# kaimat.net
KiCad netlist of a schematic drawn in EAGLE
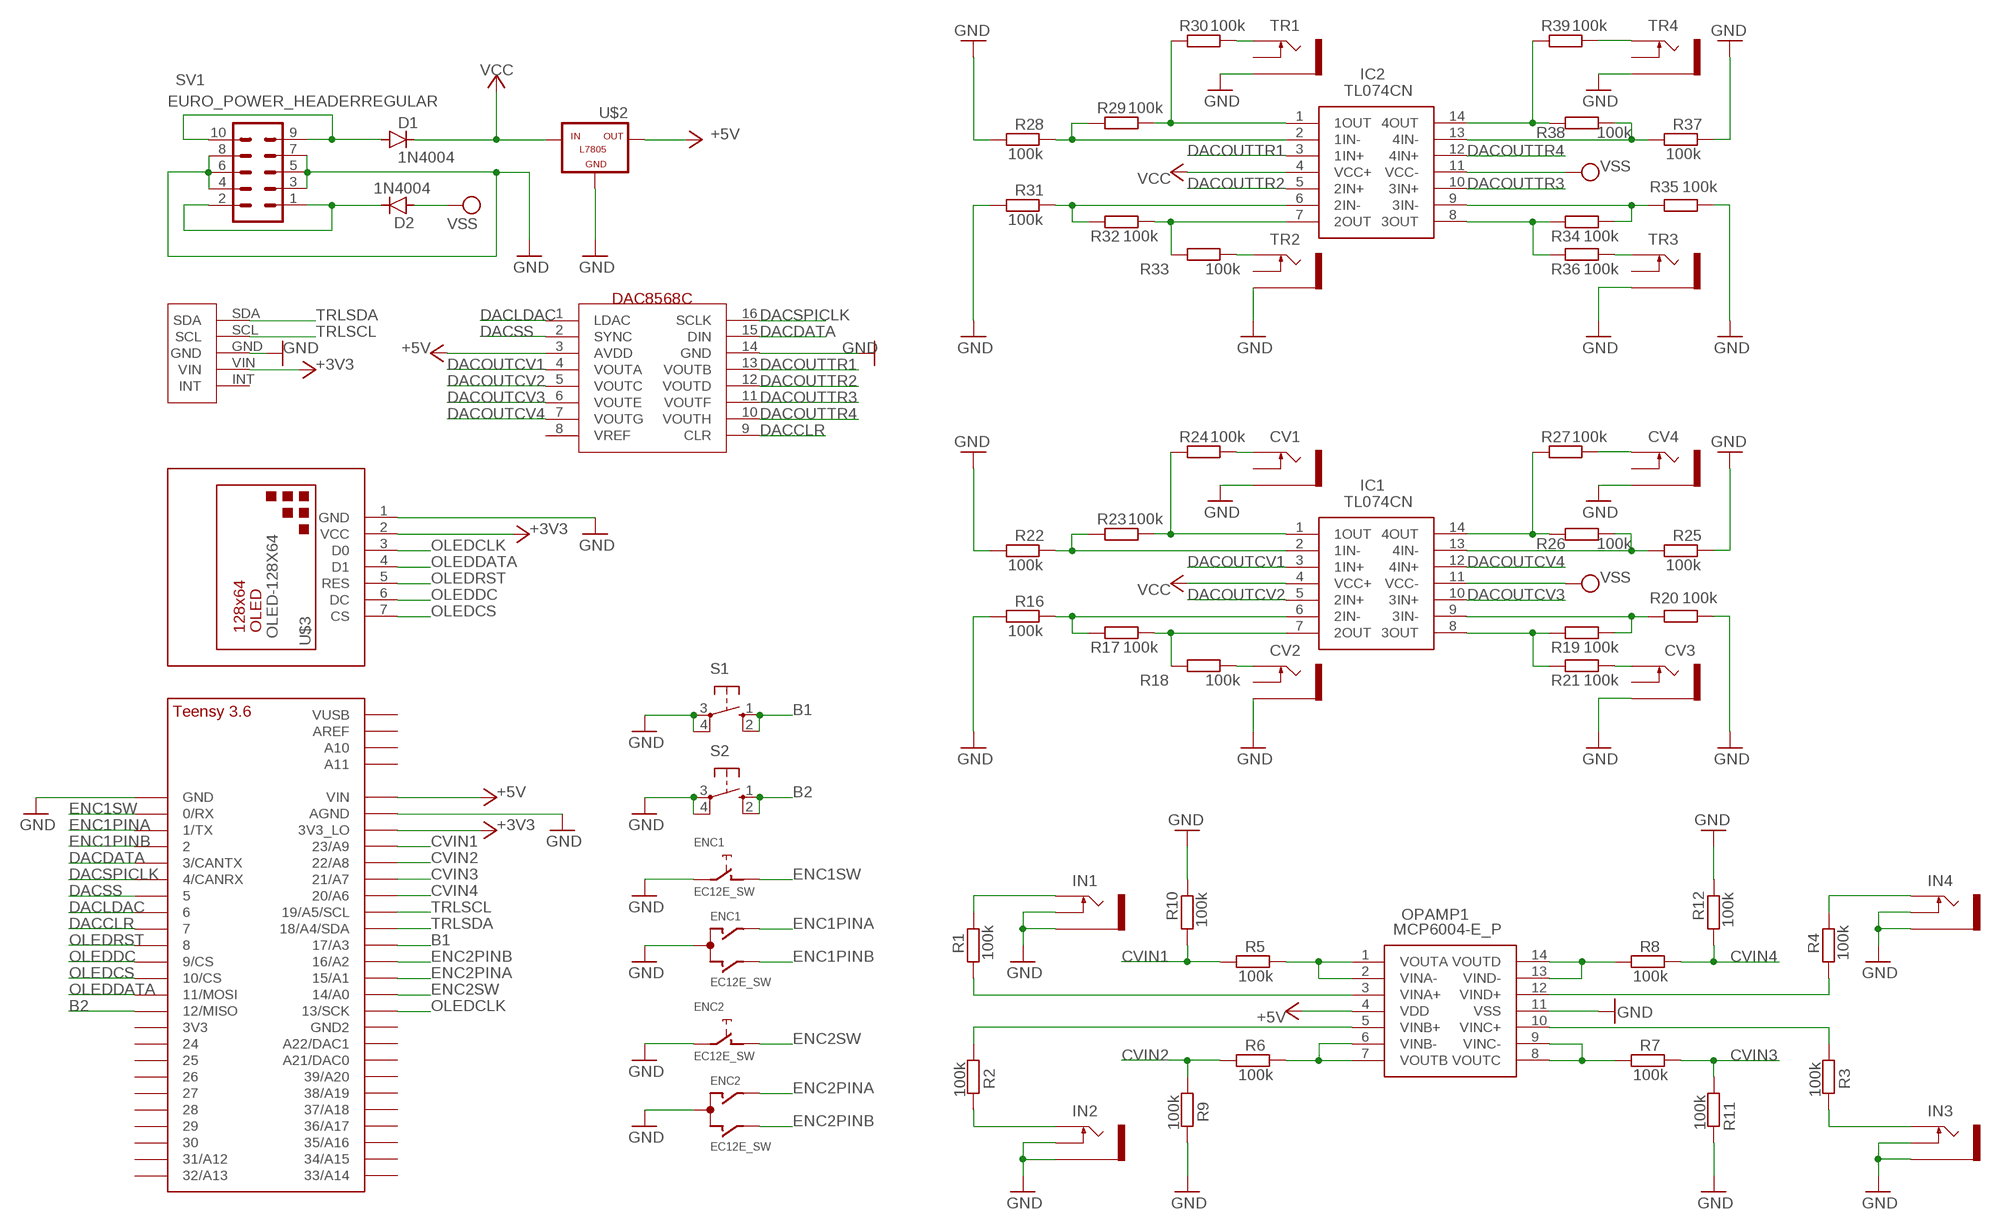
[diagram p0: schematic, sheet 1]

(export (version "E")
  (design (tool "Eeschema 10.0.6"))
  (components
    (comp (ref "CV1")
      (value "THONKICONNNEW")
      (footprint "eagle-import:WQP-PJ301M-12_JACK")
      (libsource (lib "eagle-import") (part "THONKICONNNEW"))
    )
    (comp (ref "CV2")
      (value "THONKICONNNEW")
      (footprint "eagle-import:WQP-PJ301M-12_JACK")
      (libsource (lib "eagle-import") (part "THONKICONNNEW"))
    )
    (comp (ref "CV3")
      (value "THONKICONNNEW")
      (footprint "eagle-import:WQP-PJ301M-12_JACK")
      (libsource (lib "eagle-import") (part "THONKICONNNEW"))
    )
    (comp (ref "CV4")
      (value "THONKICONNNEW")
      (footprint "eagle-import:WQP-PJ301M-12_JACK")
      (libsource (lib "eagle-import") (part "THONKICONNNEW"))
    )
    (comp (ref "D1")
      (value "1N4004")
      (footprint "eagle-import:DO41-10")
      (libsource (lib "eagle-import") (part "1N4004"))
    )
    (comp (ref "D2")
      (value "1N4004")
      (footprint "eagle-import:DO41-10")
      (libsource (lib "eagle-import") (part "1N4004"))
    )
    (comp (ref "ENC1")
      (value "EC12E_SW")
      (footprint "eagle-import:ALPS_EC12E_SW")
      (fields (field (name "MPN") "EC12E2424407"))
      (libsource (lib "eagle-import") (part "EC12E_SW"))
    )
    (comp (ref "ENC2")
      (value "EC12E_SW")
      (footprint "eagle-import:ALPS_EC12E_SW")
      (fields (field (name "MPN") "EC12E2424407"))
      (libsource (lib "eagle-import") (part "EC12E_SW"))
    )
    (comp (ref "IC1")
      (value "TL074CN")
      (footprint "eagle-import:DIP794W53P254L1930H508Q14N")
      (fields (field (name "MOUSER_PART_NUMBER") "595-TL074CN") (field (name "RS_PART_NUMBER") "0302621P"))
      (libsource (lib "eagle-import") (part "TL074CN"))
    )
    (comp (ref "IC2")
      (value "TL074CN")
      (footprint "eagle-import:DIP794W53P254L1930H508Q14N")
      (fields (field (name "MOUSER_PART_NUMBER") "595-TL074CN") (field (name "RS_PART_NUMBER") "0302621P"))
      (libsource (lib "eagle-import") (part "TL074CN"))
    )
    (comp (ref "IN1")
      (value "THONKICONNNEW")
      (footprint "eagle-import:WQP-PJ301M-12_JACK")
      (libsource (lib "eagle-import") (part "THONKICONNNEW"))
    )
    (comp (ref "IN2")
      (value "THONKICONNNEW")
      (footprint "eagle-import:WQP-PJ301M-12_JACK")
      (libsource (lib "eagle-import") (part "THONKICONNNEW"))
    )
    (comp (ref "IN3")
      (value "THONKICONNNEW")
      (footprint "eagle-import:WQP-PJ301M-12_JACK")
      (libsource (lib "eagle-import") (part "THONKICONNNEW"))
    )
    (comp (ref "IN4")
      (value "THONKICONNNEW")
      (footprint "eagle-import:WQP-PJ301M-12_JACK")
      (libsource (lib "eagle-import") (part "THONKICONNNEW"))
    )
    (comp (ref "OPAMP1")
      (value "MCP6004-E_P")
      (footprint "eagle-import:DIP781W56P254L1918H533Q14N")
      (fields
        (field (name "MANUFACTURER_PART_NUMBER") "mcp6004-e/p")
        (field (name "MOUSER_PART_NUMBER") "579-MCP6004-E/P")
        (field (name "RS_PART_NUMBER") "7386178P")
      )
      (libsource (lib "eagle-import") (part "MCP6004-E_P"))
    )
    (comp (ref "R1")
      (value "100k")
      (footprint "eagle-import:7MM_RESISTOR")
      (libsource (lib "eagle-import") (part "RESISTOR7MM"))
    )
    (comp (ref "R2")
      (value "100k")
      (footprint "eagle-import:7MM_RESISTOR")
      (libsource (lib "eagle-import") (part "RESISTOR7MM"))
    )
    (comp (ref "R3")
      (value "100k")
      (footprint "eagle-import:7MM_RESISTOR")
      (libsource (lib "eagle-import") (part "RESISTOR7MM"))
    )
    (comp (ref "R4")
      (value "100k")
      (footprint "eagle-import:7MM_RESISTOR")
      (libsource (lib "eagle-import") (part "RESISTOR7MM"))
    )
    (comp (ref "R5")
      (value "100k")
      (footprint "eagle-import:7MM_RESISTOR")
      (libsource (lib "eagle-import") (part "RESISTOR7MM"))
    )
    (comp (ref "R6")
      (value "100k")
      (footprint "eagle-import:7MM_RESISTOR")
      (libsource (lib "eagle-import") (part "RESISTOR7MM"))
    )
    (comp (ref "R7")
      (value "100k")
      (footprint "eagle-import:7MM_RESISTOR")
      (libsource (lib "eagle-import") (part "RESISTOR7MM"))
    )
    (comp (ref "R8")
      (value "100k")
      (footprint "eagle-import:7MM_RESISTOR")
      (libsource (lib "eagle-import") (part "RESISTOR7MM"))
    )
    (comp (ref "R9")
      (value "100k")
      (footprint "eagle-import:7MM_RESISTOR")
      (libsource (lib "eagle-import") (part "RESISTOR7MM"))
    )
    (comp (ref "R10")
      (value "100k")
      (footprint "eagle-import:7MM_RESISTOR")
      (libsource (lib "eagle-import") (part "RESISTOR7MM"))
    )
    (comp (ref "R11")
      (value "100k")
      (footprint "eagle-import:7MM_RESISTOR")
      (libsource (lib "eagle-import") (part "RESISTOR7MM"))
    )
    (comp (ref "R12")
      (value "100k")
      (footprint "eagle-import:7MM_RESISTOR")
      (libsource (lib "eagle-import") (part "RESISTOR7MM"))
    )
    (comp (ref "R16")
      (value "100k")
      (footprint "eagle-import:7MM_RESISTOR")
      (libsource (lib "eagle-import") (part "RESISTOR7MM"))
    )
    (comp (ref "R17")
      (value "100k")
      (footprint "eagle-import:7MM_RESISTOR")
      (libsource (lib "eagle-import") (part "RESISTOR7MM"))
    )
    (comp (ref "R18")
      (value "100k")
      (footprint "eagle-import:7MM_RESISTOR")
      (libsource (lib "eagle-import") (part "RESISTOR7MM"))
    )
    (comp (ref "R19")
      (value "100k")
      (footprint "eagle-import:7MM_RESISTOR")
      (libsource (lib "eagle-import") (part "RESISTOR7MM"))
    )
    (comp (ref "R20")
      (value "100k")
      (footprint "eagle-import:7MM_RESISTOR")
      (libsource (lib "eagle-import") (part "RESISTOR7MM"))
    )
    (comp (ref "R21")
      (value "100k")
      (footprint "eagle-import:7MM_RESISTOR")
      (libsource (lib "eagle-import") (part "RESISTOR7MM"))
    )
    (comp (ref "R22")
      (value "100k")
      (footprint "eagle-import:7MM_RESISTOR")
      (libsource (lib "eagle-import") (part "RESISTOR7MM"))
    )
    (comp (ref "R23")
      (value "100k")
      (footprint "eagle-import:7MM_RESISTOR")
      (libsource (lib "eagle-import") (part "RESISTOR7MM"))
    )
    (comp (ref "R24")
      (value "100k")
      (footprint "eagle-import:7MM_RESISTOR")
      (libsource (lib "eagle-import") (part "RESISTOR7MM"))
    )
    (comp (ref "R25")
      (value "100k")
      (footprint "eagle-import:7MM_RESISTOR")
      (libsource (lib "eagle-import") (part "RESISTOR7MM"))
    )
    (comp (ref "R26")
      (value "100k")
      (footprint "eagle-import:7MM_RESISTOR")
      (libsource (lib "eagle-import") (part "RESISTOR7MM"))
    )
    (comp (ref "R27")
      (value "100k")
      (footprint "eagle-import:7MM_RESISTOR")
      (libsource (lib "eagle-import") (part "RESISTOR7MM"))
    )
    (comp (ref "R28")
      (value "100k")
      (footprint "eagle-import:7MM_RESISTOR")
      (libsource (lib "eagle-import") (part "RESISTOR7MM"))
    )
    (comp (ref "R29")
      (value "100k")
      (footprint "eagle-import:7MM_RESISTOR")
      (libsource (lib "eagle-import") (part "RESISTOR7MM"))
    )
    (comp (ref "R30")
      (value "100k")
      (footprint "eagle-import:7MM_RESISTOR")
      (libsource (lib "eagle-import") (part "RESISTOR7MM"))
    )
    (comp (ref "R31")
      (value "100k")
      (footprint "eagle-import:7MM_RESISTOR")
      (libsource (lib "eagle-import") (part "RESISTOR7MM"))
    )
    (comp (ref "R32")
      (value "100k")
      (footprint "eagle-import:7MM_RESISTOR")
      (libsource (lib "eagle-import") (part "RESISTOR7MM"))
    )
    (comp (ref "R33")
      (value "100k")
      (footprint "eagle-import:7MM_RESISTOR")
      (libsource (lib "eagle-import") (part "RESISTOR7MM"))
    )
    (comp (ref "R34")
      (value "100k")
      (footprint "eagle-import:7MM_RESISTOR")
      (libsource (lib "eagle-import") (part "RESISTOR7MM"))
    )
    (comp (ref "R35")
      (value "100k")
      (footprint "eagle-import:7MM_RESISTOR")
      (libsource (lib "eagle-import") (part "RESISTOR7MM"))
    )
    (comp (ref "R36")
      (value "100k")
      (footprint "eagle-import:7MM_RESISTOR")
      (libsource (lib "eagle-import") (part "RESISTOR7MM"))
    )
    (comp (ref "R37")
      (value "100k")
      (footprint "eagle-import:7MM_RESISTOR")
      (libsource (lib "eagle-import") (part "RESISTOR7MM"))
    )
    (comp (ref "R38")
      (value "100k")
      (footprint "eagle-import:7MM_RESISTOR")
      (libsource (lib "eagle-import") (part "RESISTOR7MM"))
    )
    (comp (ref "R39")
      (value "100k")
      (footprint "eagle-import:7MM_RESISTOR")
      (libsource (lib "eagle-import") (part "RESISTOR7MM"))
    )
    (comp (ref "S1")
      (value "10-XX")
      (footprint "eagle-import:B3F-10XX")
      (fields (field (name "MPN") "B3F-1000"))
      (libsource (lib "eagle-import") (part "10-XX"))
    )
    (comp (ref "S2")
      (value "10-XX")
      (footprint "eagle-import:B3F-10XX")
      (fields (field (name "MPN") "B3F-1000"))
      (libsource (lib "eagle-import") (part "10-XX"))
    )
    (comp (ref "SV1")
      (value "EURO_POWER_HEADERREGULAR")
      (footprint "eagle-import:EURO_POWER_HEADER")
      (libsource (lib "eagle-import") (part "EURO_POWER_HEADERREGULAR"))
    )
    (comp (ref "TR1")
      (value "THONKICONNNEW")
      (footprint "eagle-import:WQP-PJ301M-12_JACK")
      (libsource (lib "eagle-import") (part "THONKICONNNEW"))
    )
    (comp (ref "TR2")
      (value "THONKICONNNEW")
      (footprint "eagle-import:WQP-PJ301M-12_JACK")
      (libsource (lib "eagle-import") (part "THONKICONNNEW"))
    )
    (comp (ref "TR3")
      (value "THONKICONNNEW")
      (footprint "eagle-import:WQP-PJ301M-12_JACK")
      (libsource (lib "eagle-import") (part "THONKICONNNEW"))
    )
    (comp (ref "TR4")
      (value "THONKICONNNEW")
      (footprint "eagle-import:WQP-PJ301M-12_JACK")
      (libsource (lib "eagle-import") (part "THONKICONNNEW"))
    )
    (comp (ref "U$1")
      (value "TEENSY_3.5/3.6_BASIC")
      (footprint "eagle-import:TEENSY_3.5_3.6_BASIC")
      (libsource (lib "eagle-import") (part "TEENSY_3.5/3.6_BASIC"))
    )
    (comp (ref "U$2")
      (value "-L7805")
      (footprint "eagle-import:L7805")
      (libsource (lib "eagle-import") (part "-L7805"))
    )
    (comp (ref "U$3")
      (value "OLED-128X64")
      (footprint "eagle-import:DISPLAY-OLED-128X64-SMALL")
      (libsource (lib "eagle-import") (part "OLED-128X64"))
    )
    (comp (ref "U$4")
      (value "NEOTRELLISKAIMAT2")
      (footprint "eagle-import:NEOTRELLISKAIMAT2")
      (libsource (lib "eagle-import") (part "NEOTRELLISKAIMAT2"))
    )
    (comp (ref "U$5")
      (value "DAC8568C")
      (footprint "eagle-import:TSSOP16")
      (libsource (lib "eagle-import") (part "DAC8568C"))
    )
  )
  (nets
    (net (code "1") (name "+3V3") (class "Default")
      (node (ref "U$1") (pin "3V3_LO") (pinfunction "3V3_LO_3V3_LO") (pintype "bidirectional"))
      (node (ref "U$3") (pin "2") (pinfunction "VCC_2") (pintype "power_in"))
      (node (ref "U$4") (pin "VIN") (pinfunction "VIN_VIN") (pintype "bidirectional"))
    )
    (net (code "2") (name "+5V") (class "Default")
      (node (ref "OPAMP1") (pin "4") (pinfunction "VDD_4") (pintype "power_in"))
      (node (ref "U$1") (pin "VIN") (pinfunction "VIN_VIN") (pintype "bidirectional"))
      (node (ref "U$2") (pin "OUT") (pinfunction "OUT_OUT") (pintype "passive"))
      (node (ref "U$5") (pin "3") (pinfunction "AVDD_3") (pintype "bidirectional"))
    )
    (net (code "3") (name "/B1") (class "Default")
      (node (ref "S1") (pin "1") (pinfunction "S_1") (pintype "passive"))
      (node (ref "S1") (pin "2") (pinfunction "S1_2") (pintype "passive"))
      (node (ref "U$1") (pin "17/A3") (pinfunction "17/A3_17/A3") (pintype "bidirectional"))
    )
    (net (code "4") (name "/B2") (class "Default")
      (node (ref "S2") (pin "1") (pinfunction "S_1") (pintype "passive"))
      (node (ref "S2") (pin "2") (pinfunction "S1_2") (pintype "passive"))
      (node (ref "U$1") (pin "12/MISO") (pinfunction "12/MISO_12/MISO") (pintype "bidirectional"))
    )
    (net (code "5") (name "/CVIN1") (class "Default")
      (node (ref "R10") (pin "1") (pinfunction "1_1") (pintype "passive"))
      (node (ref "R5") (pin "1") (pinfunction "1_1") (pintype "passive"))
      (node (ref "U$1") (pin "23/A9") (pinfunction "23/A9_23/A9") (pintype "bidirectional"))
    )
    (net (code "6") (name "/CVIN2") (class "Default")
      (node (ref "R6") (pin "1") (pinfunction "1_1") (pintype "passive"))
      (node (ref "R9") (pin "1") (pinfunction "1_1") (pintype "passive"))
      (node (ref "U$1") (pin "22/A8") (pinfunction "22/A8_22/A8") (pintype "bidirectional"))
    )
    (net (code "7") (name "/CVIN3") (class "Default")
      (node (ref "R11") (pin "1") (pinfunction "1_1") (pintype "passive"))
      (node (ref "R7") (pin "2") (pinfunction "2_2") (pintype "passive"))
      (node (ref "U$1") (pin "21/A7") (pinfunction "21/A7_21/A7") (pintype "bidirectional"))
    )
    (net (code "8") (name "/CVIN4") (class "Default")
      (node (ref "R12") (pin "1") (pinfunction "1_1") (pintype "passive"))
      (node (ref "R8") (pin "2") (pinfunction "2_2") (pintype "passive"))
      (node (ref "U$1") (pin "20/A6") (pinfunction "20/A6_20/A6") (pintype "bidirectional"))
    )
    (net (code "9") (name "/DACCLR") (class "Default")
      (node (ref "U$1") (pin "7") (pinfunction "7_7") (pintype "bidirectional"))
      (node (ref "U$5") (pin "9") (pinfunction "CLR_9") (pintype "bidirectional"))
    )
    (net (code "10") (name "/DACDATA") (class "Default")
      (node (ref "U$1") (pin "3/CANTX") (pinfunction "3/CANTX_3/CANTX") (pintype "bidirectional"))
      (node (ref "U$5") (pin "15") (pinfunction "DIN_15") (pintype "bidirectional"))
    )
    (net (code "11") (name "/DACLDAC") (class "Default")
      (node (ref "U$1") (pin "6") (pinfunction "6_6") (pintype "bidirectional"))
      (node (ref "U$5") (pin "1") (pinfunction "LDAC_1") (pintype "bidirectional"))
    )
    (net (code "12") (name "/DACOUTCV1") (class "Default")
      (node (ref "IC1") (pin "3") (pinfunction "1IN+_3") (pintype "input"))
      (node (ref "U$5") (pin "4") (pinfunction "VOUTA_4") (pintype "bidirectional"))
    )
    (net (code "13") (name "/DACOUTCV2") (class "Default")
      (node (ref "IC1") (pin "5") (pinfunction "2IN+_5") (pintype "input"))
      (node (ref "U$5") (pin "5") (pinfunction "VOUTC_5") (pintype "bidirectional"))
    )
    (net (code "14") (name "/DACOUTCV3") (class "Default")
      (node (ref "IC1") (pin "10") (pinfunction "3IN+_10") (pintype "input"))
      (node (ref "U$5") (pin "6") (pinfunction "VOUTE_6") (pintype "bidirectional"))
    )
    (net (code "15") (name "/DACOUTCV4") (class "Default")
      (node (ref "IC1") (pin "12") (pinfunction "4IN+_12") (pintype "input"))
      (node (ref "U$5") (pin "7") (pinfunction "VOUTG_7") (pintype "bidirectional"))
    )
    (net (code "16") (name "/DACOUTTR1") (class "Default")
      (node (ref "IC2") (pin "3") (pinfunction "1IN+_3") (pintype "input"))
      (node (ref "U$5") (pin "13") (pinfunction "VOUTB_13") (pintype "bidirectional"))
    )
    (net (code "17") (name "/DACOUTTR2") (class "Default")
      (node (ref "IC2") (pin "5") (pinfunction "2IN+_5") (pintype "input"))
      (node (ref "U$5") (pin "12") (pinfunction "VOUTD_12") (pintype "bidirectional"))
    )
    (net (code "18") (name "/DACOUTTR3") (class "Default")
      (node (ref "IC2") (pin "10") (pinfunction "3IN+_10") (pintype "input"))
      (node (ref "U$5") (pin "11") (pinfunction "VOUTF_11") (pintype "bidirectional"))
    )
    (net (code "19") (name "/DACOUTTR4") (class "Default")
      (node (ref "IC2") (pin "12") (pinfunction "4IN+_12") (pintype "input"))
      (node (ref "U$5") (pin "10") (pinfunction "VOUTH_10") (pintype "bidirectional"))
    )
    (net (code "20") (name "/DACSPICLK") (class "Default")
      (node (ref "U$1") (pin "4/CANRX") (pinfunction "4/CANRX_4/CANRX") (pintype "bidirectional"))
      (node (ref "U$5") (pin "16") (pinfunction "SCLK_16") (pintype "bidirectional"))
    )
    (net (code "21") (name "/DACSS") (class "Default")
      (node (ref "U$1") (pin "5") (pinfunction "5_5") (pintype "bidirectional"))
      (node (ref "U$5") (pin "2") (pinfunction "SYNC_2") (pintype "bidirectional"))
    )
    (net (code "22") (name "/ENC1PINA") (class "Default")
      (node (ref "ENC1") (pin "A") (pinfunction "A_A") (pintype "passive"))
      (node (ref "U$1") (pin "1/TX") (pinfunction "1/TX_1/TX") (pintype "bidirectional"))
    )
    (net (code "23") (name "/ENC1PINB") (class "Default")
      (node (ref "ENC1") (pin "B") (pinfunction "B_B") (pintype "passive"))
      (node (ref "U$1") (pin "2") (pinfunction "2_2") (pintype "bidirectional"))
    )
    (net (code "24") (name "/ENC1SW") (class "Default")
      (node (ref "ENC1") (pin "D") (pinfunction "1_D") (pintype "passive"))
      (node (ref "U$1") (pin "0/RX") (pinfunction "0/RX_0/RX") (pintype "bidirectional"))
    )
    (net (code "25") (name "/ENC2PINA") (class "Default")
      (node (ref "ENC2") (pin "A") (pinfunction "A_A") (pintype "passive"))
      (node (ref "U$1") (pin "15/A1") (pinfunction "15/A1_15/A1") (pintype "bidirectional"))
    )
    (net (code "26") (name "/ENC2PINB") (class "Default")
      (node (ref "ENC2") (pin "B") (pinfunction "B_B") (pintype "passive"))
      (node (ref "U$1") (pin "16/A2") (pinfunction "16/A2_16/A2") (pintype "bidirectional"))
    )
    (net (code "27") (name "/ENC2SW") (class "Default")
      (node (ref "ENC2") (pin "D") (pinfunction "1_D") (pintype "passive"))
      (node (ref "U$1") (pin "14/A0") (pinfunction "14/A0_14/A0") (pintype "bidirectional"))
    )
    (net (code "28") (name "/OLEDCLK") (class "Default")
      (node (ref "U$1") (pin "13/SCK") (pinfunction "13/SCK_13/SCK") (pintype "bidirectional"))
      (node (ref "U$3") (pin "3") (pinfunction "D0_3") (pintype "bidirectional"))
    )
    (net (code "29") (name "/OLEDCS") (class "Default")
      (node (ref "U$1") (pin "10/CS") (pinfunction "10/CS_10/CS") (pintype "bidirectional"))
      (node (ref "U$3") (pin "7") (pinfunction "CS_7") (pintype "bidirectional"))
    )
    (net (code "30") (name "/OLEDDATA") (class "Default")
      (node (ref "U$1") (pin "11/MOSI") (pinfunction "11/MOSI_11/MOSI") (pintype "bidirectional"))
      (node (ref "U$3") (pin "4") (pinfunction "D1_4") (pintype "bidirectional"))
    )
    (net (code "31") (name "/OLEDDC") (class "Default")
      (node (ref "U$1") (pin "9/CS") (pinfunction "9/CS_9/CS") (pintype "bidirectional"))
      (node (ref "U$3") (pin "6") (pinfunction "DC_6") (pintype "bidirectional"))
    )
    (net (code "32") (name "/OLEDRST") (class "Default")
      (node (ref "U$1") (pin "8") (pinfunction "8_8") (pintype "bidirectional"))
      (node (ref "U$3") (pin "5") (pinfunction "RES_5") (pintype "bidirectional"))
    )
    (net (code "33") (name "/TRLSCL") (class "Default")
      (node (ref "U$1") (pin "19/A5/SCL") (pinfunction "19/A5/SCL_19/A5/SCL") (pintype "bidirectional"))
      (node (ref "U$4") (pin "SCL") (pinfunction "SCL_SCL") (pintype "bidirectional"))
    )
    (net (code "34") (name "/TRLSDA") (class "Default")
      (node (ref "U$1") (pin "18/A4/SDA") (pinfunction "18/A4/SDA_18/A4/SDA") (pintype "bidirectional"))
      (node (ref "U$4") (pin "SDA") (pinfunction "SDA_SDA") (pintype "bidirectional"))
    )
    (net (code "35") (name "GND") (class "Default")
      (node (ref "CV1") (pin "P$3_SLEEVE") (pinfunction "SLEEVE_P$3_SLEEVE") (pintype "passive"))
      (node (ref "CV2") (pin "P$3_SLEEVE") (pinfunction "SLEEVE_P$3_SLEEVE") (pintype "passive"))
      (node (ref "CV3") (pin "P$3_SLEEVE") (pinfunction "SLEEVE_P$3_SLEEVE") (pintype "passive"))
      (node (ref "CV4") (pin "P$3_SLEEVE") (pinfunction "SLEEVE_P$3_SLEEVE") (pintype "passive"))
      (node (ref "ENC1") (pin "C") (pinfunction "C_C") (pintype "passive"))
      (node (ref "ENC1") (pin "E") (pinfunction "2_E") (pintype "passive"))
      (node (ref "ENC2") (pin "C") (pinfunction "C_C") (pintype "passive"))
      (node (ref "ENC2") (pin "E") (pinfunction "2_E") (pintype "passive"))
      (node (ref "IN1") (pin "P$2_SWITCH") (pinfunction "SWITCH_P$2_SWITCH") (pintype "passive"))
      (node (ref "IN1") (pin "P$3_SLEEVE") (pinfunction "SLEEVE_P$3_SLEEVE") (pintype "passive"))
      (node (ref "IN2") (pin "P$2_SWITCH") (pinfunction "SWITCH_P$2_SWITCH") (pintype "passive"))
      (node (ref "IN2") (pin "P$3_SLEEVE") (pinfunction "SLEEVE_P$3_SLEEVE") (pintype "passive"))
      (node (ref "IN3") (pin "P$2_SWITCH") (pinfunction "SWITCH_P$2_SWITCH") (pintype "passive"))
      (node (ref "IN3") (pin "P$3_SLEEVE") (pinfunction "SLEEVE_P$3_SLEEVE") (pintype "passive"))
      (node (ref "IN4") (pin "P$2_SWITCH") (pinfunction "SWITCH_P$2_SWITCH") (pintype "passive"))
      (node (ref "IN4") (pin "P$3_SLEEVE") (pinfunction "SLEEVE_P$3_SLEEVE") (pintype "passive"))
      (node (ref "OPAMP1") (pin "11") (pinfunction "VSS_11") (pintype "power_in"))
      (node (ref "R10") (pin "2") (pinfunction "2_2") (pintype "passive"))
      (node (ref "R11") (pin "2") (pinfunction "2_2") (pintype "passive"))
      (node (ref "R12") (pin "2") (pinfunction "2_2") (pintype "passive"))
      (node (ref "R16") (pin "1") (pinfunction "1_1") (pintype "passive"))
      (node (ref "R20") (pin "2") (pinfunction "2_2") (pintype "passive"))
      (node (ref "R22") (pin "1") (pinfunction "1_1") (pintype "passive"))
      (node (ref "R25") (pin "2") (pinfunction "2_2") (pintype "passive"))
      (node (ref "R28") (pin "1") (pinfunction "1_1") (pintype "passive"))
      (node (ref "R31") (pin "1") (pinfunction "1_1") (pintype "passive"))
      (node (ref "R35") (pin "2") (pinfunction "2_2") (pintype "passive"))
      (node (ref "R37") (pin "2") (pinfunction "2_2") (pintype "passive"))
      (node (ref "R9") (pin "2") (pinfunction "2_2") (pintype "passive"))
      (node (ref "S1") (pin "3") (pinfunction "P_3") (pintype "passive"))
      (node (ref "S1") (pin "4") (pinfunction "P1_4") (pintype "passive"))
      (node (ref "S2") (pin "3") (pinfunction "P_3") (pintype "passive"))
      (node (ref "S2") (pin "4") (pinfunction "P1_4") (pintype "passive"))
      (node (ref "SV1") (pin "3") (pinfunction "3_3") (pintype "passive"))
      (node (ref "SV1") (pin "4") (pinfunction "4_4") (pintype "passive"))
      (node (ref "SV1") (pin "5") (pinfunction "5_5") (pintype "passive"))
      (node (ref "SV1") (pin "6") (pinfunction "6_6") (pintype "passive"))
      (node (ref "SV1") (pin "7") (pinfunction "7_7") (pintype "passive"))
      (node (ref "SV1") (pin "8") (pinfunction "8_8") (pintype "passive"))
      (node (ref "TR1") (pin "P$3_SLEEVE") (pinfunction "SLEEVE_P$3_SLEEVE") (pintype "passive"))
      (node (ref "TR2") (pin "P$3_SLEEVE") (pinfunction "SLEEVE_P$3_SLEEVE") (pintype "passive"))
      (node (ref "TR3") (pin "P$3_SLEEVE") (pinfunction "SLEEVE_P$3_SLEEVE") (pintype "passive"))
      (node (ref "TR4") (pin "P$3_SLEEVE") (pinfunction "SLEEVE_P$3_SLEEVE") (pintype "passive"))
      (node (ref "U$1") (pin "AGND") (pinfunction "AGND_AGND") (pintype "bidirectional"))
      (node (ref "U$1") (pin "GND") (pinfunction "GND_GND") (pintype "bidirectional"))
      (node (ref "U$2") (pin "GND") (pinfunction "GND_GND") (pintype "input"))
      (node (ref "U$3") (pin "1") (pinfunction "GND_1") (pintype "power_in"))
      (node (ref "U$4") (pin "GND") (pinfunction "GND_GND") (pintype "bidirectional"))
      (node (ref "U$5") (pin "14") (pinfunction "GND_14") (pintype "bidirectional"))
    )
    (net (code "36") (name "Net-(CV1-TIP)") (class "Default")
      (node (ref "CV1") (pin "P$1_TIP") (pinfunction "TIP_P$1_TIP") (pintype "passive"))
      (node (ref "R24") (pin "2") (pinfunction "2_2") (pintype "passive"))
    )
    (net (code "37") (name "Net-(CV2-TIP)") (class "Default")
      (node (ref "CV2") (pin "P$1_TIP") (pinfunction "TIP_P$1_TIP") (pintype "passive"))
      (node (ref "R18") (pin "2") (pinfunction "2_2") (pintype "passive"))
    )
    (net (code "38") (name "Net-(CV3-TIP)") (class "Default")
      (node (ref "CV3") (pin "P$1_TIP") (pinfunction "TIP_P$1_TIP") (pintype "passive"))
      (node (ref "R21") (pin "2") (pinfunction "2_2") (pintype "passive"))
    )
    (net (code "39") (name "Net-(CV4-TIP)") (class "Default")
      (node (ref "CV4") (pin "P$1_TIP") (pinfunction "TIP_P$1_TIP") (pintype "passive"))
      (node (ref "R27") (pin "2") (pinfunction "2_2") (pintype "passive"))
    )
    (net (code "40") (name "Net-(D1-PadA)") (class "Default")
      (node (ref "D1") (pin "A") (pinfunction "A_A") (pintype "passive"))
      (node (ref "SV1") (pin "10") (pinfunction "10_10") (pintype "passive"))
      (node (ref "SV1") (pin "9") (pinfunction "9_9") (pintype "passive"))
    )
    (net (code "41") (name "Net-(D2-PadC)") (class "Default")
      (node (ref "D2") (pin "C") (pinfunction "C_C") (pintype "passive"))
      (node (ref "SV1") (pin "1") (pinfunction "1_1") (pintype "passive"))
      (node (ref "SV1") (pin "2") (pinfunction "2_2") (pintype "passive"))
    )
    (net (code "42") (name "Net-(IC1-1IN-)") (class "Default")
      (node (ref "IC1") (pin "2") (pinfunction "1IN-_2") (pintype "input"))
      (node (ref "R22") (pin "2") (pinfunction "2_2") (pintype "passive"))
      (node (ref "R23") (pin "1") (pinfunction "1_1") (pintype "passive"))
    )
    (net (code "43") (name "Net-(IC1-1OUT)") (class "Default")
      (node (ref "IC1") (pin "1") (pinfunction "1OUT_1") (pintype "output"))
      (node (ref "R23") (pin "2") (pinfunction "2_2") (pintype "passive"))
      (node (ref "R24") (pin "1") (pinfunction "1_1") (pintype "passive"))
    )
    (net (code "44") (name "Net-(IC1-2IN-)") (class "Default")
      (node (ref "IC1") (pin "6") (pinfunction "2IN-_6") (pintype "input"))
      (node (ref "R16") (pin "2") (pinfunction "2_2") (pintype "passive"))
      (node (ref "R17") (pin "1") (pinfunction "1_1") (pintype "passive"))
    )
    (net (code "45") (name "Net-(IC1-2OUT)") (class "Default")
      (node (ref "IC1") (pin "7") (pinfunction "2OUT_7") (pintype "output"))
      (node (ref "R17") (pin "2") (pinfunction "2_2") (pintype "passive"))
      (node (ref "R18") (pin "1") (pinfunction "1_1") (pintype "passive"))
    )
    (net (code "46") (name "Net-(IC1-3IN-)") (class "Default")
      (node (ref "IC1") (pin "9") (pinfunction "3IN-_9") (pintype "input"))
      (node (ref "R19") (pin "2") (pinfunction "2_2") (pintype "passive"))
      (node (ref "R20") (pin "1") (pinfunction "1_1") (pintype "passive"))
    )
    (net (code "47") (name "Net-(IC1-3OUT)") (class "Default")
      (node (ref "IC1") (pin "8") (pinfunction "3OUT_8") (pintype "output"))
      (node (ref "R19") (pin "1") (pinfunction "1_1") (pintype "passive"))
      (node (ref "R21") (pin "1") (pinfunction "1_1") (pintype "passive"))
    )
    (net (code "48") (name "Net-(IC1-4IN-)") (class "Default")
      (node (ref "IC1") (pin "13") (pinfunction "4IN-_13") (pintype "input"))
      (node (ref "R25") (pin "1") (pinfunction "1_1") (pintype "passive"))
      (node (ref "R26") (pin "2") (pinfunction "2_2") (pintype "passive"))
    )
    (net (code "49") (name "Net-(IC1-4OUT)") (class "Default")
      (node (ref "IC1") (pin "14") (pinfunction "4OUT_14") (pintype "output"))
      (node (ref "R26") (pin "1") (pinfunction "1_1") (pintype "passive"))
      (node (ref "R27") (pin "1") (pinfunction "1_1") (pintype "passive"))
    )
    (net (code "50") (name "Net-(IC2-1IN-)") (class "Default")
      (node (ref "IC2") (pin "2") (pinfunction "1IN-_2") (pintype "input"))
      (node (ref "R28") (pin "2") (pinfunction "2_2") (pintype "passive"))
      (node (ref "R29") (pin "1") (pinfunction "1_1") (pintype "passive"))
    )
    (net (code "51") (name "Net-(IC2-1OUT)") (class "Default")
      (node (ref "IC2") (pin "1") (pinfunction "1OUT_1") (pintype "output"))
      (node (ref "R29") (pin "2") (pinfunction "2_2") (pintype "passive"))
      (node (ref "R30") (pin "1") (pinfunction "1_1") (pintype "passive"))
    )
    (net (code "52") (name "Net-(IC2-2IN-)") (class "Default")
      (node (ref "IC2") (pin "6") (pinfunction "2IN-_6") (pintype "input"))
      (node (ref "R31") (pin "2") (pinfunction "2_2") (pintype "passive"))
      (node (ref "R32") (pin "1") (pinfunction "1_1") (pintype "passive"))
    )
    (net (code "53") (name "Net-(IC2-2OUT)") (class "Default")
      (node (ref "IC2") (pin "7") (pinfunction "2OUT_7") (pintype "output"))
      (node (ref "R32") (pin "2") (pinfunction "2_2") (pintype "passive"))
      (node (ref "R33") (pin "1") (pinfunction "1_1") (pintype "passive"))
    )
    (net (code "54") (name "Net-(IC2-3IN-)") (class "Default")
      (node (ref "IC2") (pin "9") (pinfunction "3IN-_9") (pintype "input"))
      (node (ref "R34") (pin "2") (pinfunction "2_2") (pintype "passive"))
      (node (ref "R35") (pin "1") (pinfunction "1_1") (pintype "passive"))
    )
    (net (code "55") (name "Net-(IC2-3OUT)") (class "Default")
      (node (ref "IC2") (pin "8") (pinfunction "3OUT_8") (pintype "output"))
      (node (ref "R34") (pin "1") (pinfunction "1_1") (pintype "passive"))
      (node (ref "R36") (pin "1") (pinfunction "1_1") (pintype "passive"))
    )
    (net (code "56") (name "Net-(IC2-4IN-)") (class "Default")
      (node (ref "IC2") (pin "13") (pinfunction "4IN-_13") (pintype "input"))
      (node (ref "R37") (pin "1") (pinfunction "1_1") (pintype "passive"))
      (node (ref "R38") (pin "2") (pinfunction "2_2") (pintype "passive"))
    )
    (net (code "57") (name "Net-(IC2-4OUT)") (class "Default")
      (node (ref "IC2") (pin "14") (pinfunction "4OUT_14") (pintype "output"))
      (node (ref "R38") (pin "1") (pinfunction "1_1") (pintype "passive"))
      (node (ref "R39") (pin "1") (pinfunction "1_1") (pintype "passive"))
    )
    (net (code "58") (name "Net-(IN1-TIP)") (class "Default")
      (node (ref "IN1") (pin "P$1_TIP") (pinfunction "TIP_P$1_TIP") (pintype "passive"))
      (node (ref "R1") (pin "2") (pinfunction "2_2") (pintype "passive"))
    )
    (net (code "59") (name "Net-(IN2-TIP)") (class "Default")
      (node (ref "IN2") (pin "P$1_TIP") (pinfunction "TIP_P$1_TIP") (pintype "passive"))
      (node (ref "R2") (pin "2") (pinfunction "2_2") (pintype "passive"))
    )
    (net (code "60") (name "Net-(IN3-TIP)") (class "Default")
      (node (ref "IN3") (pin "P$1_TIP") (pinfunction "TIP_P$1_TIP") (pintype "passive"))
      (node (ref "R3") (pin "2") (pinfunction "2_2") (pintype "passive"))
    )
    (net (code "61") (name "Net-(IN4-TIP)") (class "Default")
      (node (ref "IN4") (pin "P$1_TIP") (pinfunction "TIP_P$1_TIP") (pintype "passive"))
      (node (ref "R4") (pin "2") (pinfunction "2_2") (pintype "passive"))
    )
    (net (code "62") (name "Net-(OPAMP1-VINA+)") (class "Default")
      (node (ref "OPAMP1") (pin "3") (pinfunction "VINA+_3") (pintype "input"))
      (node (ref "R1") (pin "1") (pinfunction "1_1") (pintype "passive"))
    )
    (net (code "63") (name "Net-(OPAMP1-VINA-)") (class "Default")
      (node (ref "OPAMP1") (pin "1") (pinfunction "VOUTA_1") (pintype "output"))
      (node (ref "OPAMP1") (pin "2") (pinfunction "VINA-_2") (pintype "input"))
      (node (ref "R5") (pin "2") (pinfunction "2_2") (pintype "passive"))
    )
    (net (code "64") (name "Net-(OPAMP1-VINB+)") (class "Default")
      (node (ref "OPAMP1") (pin "5") (pinfunction "VINB+_5") (pintype "input"))
      (node (ref "R2") (pin "1") (pinfunction "1_1") (pintype "passive"))
    )
    (net (code "65") (name "Net-(OPAMP1-VINB-)") (class "Default")
      (node (ref "OPAMP1") (pin "6") (pinfunction "VINB-_6") (pintype "input"))
      (node (ref "OPAMP1") (pin "7") (pinfunction "VOUTB_7") (pintype "output"))
      (node (ref "R6") (pin "2") (pinfunction "2_2") (pintype "passive"))
    )
    (net (code "66") (name "Net-(OPAMP1-VINC+)") (class "Default")
      (node (ref "OPAMP1") (pin "10") (pinfunction "VINC+_10") (pintype "input"))
      (node (ref "R3") (pin "1") (pinfunction "1_1") (pintype "passive"))
    )
    (net (code "67") (name "Net-(OPAMP1-VINC-)") (class "Default")
      (node (ref "OPAMP1") (pin "8") (pinfunction "VOUTC_8") (pintype "output"))
      (node (ref "OPAMP1") (pin "9") (pinfunction "VINC-_9") (pintype "input"))
      (node (ref "R7") (pin "1") (pinfunction "1_1") (pintype "passive"))
    )
    (net (code "68") (name "Net-(OPAMP1-VIND+)") (class "Default")
      (node (ref "OPAMP1") (pin "12") (pinfunction "VIND+_12") (pintype "input"))
      (node (ref "R4") (pin "1") (pinfunction "1_1") (pintype "passive"))
    )
    (net (code "69") (name "Net-(OPAMP1-VIND-)") (class "Default")
      (node (ref "OPAMP1") (pin "13") (pinfunction "VIND-_13") (pintype "input"))
      (node (ref "OPAMP1") (pin "14") (pinfunction "VOUTD_14") (pintype "output"))
      (node (ref "R8") (pin "1") (pinfunction "1_1") (pintype "passive"))
    )
    (net (code "70") (name "Net-(TR1-TIP)") (class "Default")
      (node (ref "R30") (pin "2") (pinfunction "2_2") (pintype "passive"))
      (node (ref "TR1") (pin "P$1_TIP") (pinfunction "TIP_P$1_TIP") (pintype "passive"))
    )
    (net (code "71") (name "Net-(TR2-TIP)") (class "Default")
      (node (ref "R33") (pin "2") (pinfunction "2_2") (pintype "passive"))
      (node (ref "TR2") (pin "P$1_TIP") (pinfunction "TIP_P$1_TIP") (pintype "passive"))
    )
    (net (code "72") (name "Net-(TR3-TIP)") (class "Default")
      (node (ref "R36") (pin "2") (pinfunction "2_2") (pintype "passive"))
      (node (ref "TR3") (pin "P$1_TIP") (pinfunction "TIP_P$1_TIP") (pintype "passive"))
    )
    (net (code "73") (name "Net-(TR4-TIP)") (class "Default")
      (node (ref "R39") (pin "2") (pinfunction "2_2") (pintype "passive"))
      (node (ref "TR4") (pin "P$1_TIP") (pinfunction "TIP_P$1_TIP") (pintype "passive"))
    )
    (net (code "74") (name "VCC") (class "Default")
      (node (ref "D1") (pin "C") (pinfunction "C_C") (pintype "passive"))
      (node (ref "IC1") (pin "4") (pinfunction "VCC+_4") (pintype "power_in"))
      (node (ref "IC2") (pin "4") (pinfunction "VCC+_4") (pintype "power_in"))
      (node (ref "U$2") (pin "IN") (pinfunction "IN_IN") (pintype "input"))
    )
    (net (code "75") (name "VSS") (class "Default")
      (node (ref "D2") (pin "A") (pinfunction "A_A") (pintype "passive"))
      (node (ref "IC1") (pin "11") (pinfunction "VCC-_11") (pintype "power_in"))
      (node (ref "IC2") (pin "11") (pinfunction "VCC-_11") (pintype "power_in"))
    )
    (net (code "76") (name "unconnected-(CV1-SWITCH-PadP$2_SWITCH)") (class "Default")
      (node (ref "CV1") (pin "P$2_SWITCH") (pinfunction "SWITCH_P$2_SWITCH") (pintype "passive"))
    )
    (net (code "77") (name "unconnected-(CV2-SWITCH-PadP$2_SWITCH)") (class "Default")
      (node (ref "CV2") (pin "P$2_SWITCH") (pinfunction "SWITCH_P$2_SWITCH") (pintype "passive"))
    )
    (net (code "78") (name "unconnected-(CV3-SWITCH-PadP$2_SWITCH)") (class "Default")
      (node (ref "CV3") (pin "P$2_SWITCH") (pinfunction "SWITCH_P$2_SWITCH") (pintype "passive"))
    )
    (net (code "79") (name "unconnected-(CV4-SWITCH-PadP$2_SWITCH)") (class "Default")
      (node (ref "CV4") (pin "P$2_SWITCH") (pinfunction "SWITCH_P$2_SWITCH") (pintype "passive"))
    )
    (net (code "80") (name "unconnected-(TR1-SWITCH-PadP$2_SWITCH)") (class "Default")
      (node (ref "TR1") (pin "P$2_SWITCH") (pinfunction "SWITCH_P$2_SWITCH") (pintype "passive"))
    )
    (net (code "81") (name "unconnected-(TR2-SWITCH-PadP$2_SWITCH)") (class "Default")
      (node (ref "TR2") (pin "P$2_SWITCH") (pinfunction "SWITCH_P$2_SWITCH") (pintype "passive"))
    )
    (net (code "82") (name "unconnected-(TR3-SWITCH-PadP$2_SWITCH)") (class "Default")
      (node (ref "TR3") (pin "P$2_SWITCH") (pinfunction "SWITCH_P$2_SWITCH") (pintype "passive"))
    )
    (net (code "83") (name "unconnected-(TR4-SWITCH-PadP$2_SWITCH)") (class "Default")
      (node (ref "TR4") (pin "P$2_SWITCH") (pinfunction "SWITCH_P$2_SWITCH") (pintype "passive"))
    )
    (net (code "84") (name "unconnected-(U$1-A21{slash}DAC0-Pad21{slash}DAC0)") (class "Default")
      (node (ref "U$1") (pin "21/DAC0") (pinfunction "A21/DAC0_21/DAC0") (pintype "bidirectional"))
    )
    (net (code "85") (name "unconnected-(U$1-Pad3V3)") (class "Default")
      (node (ref "U$1") (pin "3V3") (pinfunction "3V3_3V3") (pintype "bidirectional"))
    )
    (net (code "86") (name "unconnected-(U$1-Pad24)") (class "Default")
      (node (ref "U$1") (pin "24") (pinfunction "24_24") (pintype "bidirectional"))
    )
    (net (code "87") (name "unconnected-(U$1-Pad25)") (class "Default")
      (node (ref "U$1") (pin "25") (pinfunction "25_25") (pintype "bidirectional"))
    )
    (net (code "88") (name "unconnected-(U$1-Pad26)") (class "Default")
      (node (ref "U$1") (pin "26") (pinfunction "26_26") (pintype "bidirectional"))
    )
    (net (code "89") (name "unconnected-(U$1-Pad27)") (class "Default")
      (node (ref "U$1") (pin "27") (pinfunction "27_27") (pintype "bidirectional"))
    )
    (net (code "90") (name "unconnected-(U$1-Pad28)") (class "Default")
      (node (ref "U$1") (pin "28") (pinfunction "28_28") (pintype "bidirectional"))
    )
    (net (code "91") (name "unconnected-(U$1-Pad29)") (class "Default")
      (node (ref "U$1") (pin "29") (pinfunction "29_29") (pintype "bidirectional"))
    )
    (net (code "92") (name "unconnected-(U$1-Pad30)") (class "Default")
      (node (ref "U$1") (pin "30") (pinfunction "30_30") (pintype "bidirectional"))
    )
    (net (code "93") (name "unconnected-(U$1-Pad31{slash}A12)") (class "Default")
      (node (ref "U$1") (pin "31/A12") (pinfunction "31/A12_31/A12") (pintype "bidirectional"))
    )
    (net (code "94") (name "unconnected-(U$1-Pad32{slash}A13)") (class "Default")
      (node (ref "U$1") (pin "32/A13") (pinfunction "32/A13_32/A13") (pintype "bidirectional"))
    )
    (net (code "95") (name "unconnected-(U$1-Pad33{slash}A14)") (class "Default")
      (node (ref "U$1") (pin "33/A14") (pinfunction "33/A14_33/A14") (pintype "bidirectional"))
    )
    (net (code "96") (name "unconnected-(U$1-Pad34{slash}A15)") (class "Default")
      (node (ref "U$1") (pin "34/A15") (pinfunction "34/A15_34/A15") (pintype "bidirectional"))
    )
    (net (code "97") (name "unconnected-(U$1-Pad35{slash}A16)") (class "Default")
      (node (ref "U$1") (pin "35/A16") (pinfunction "35/A16_35/A16") (pintype "bidirectional"))
    )
    (net (code "98") (name "unconnected-(U$1-Pad36{slash}A17)") (class "Default")
      (node (ref "U$1") (pin "36/A17") (pinfunction "36/A17_36/A17") (pintype "bidirectional"))
    )
    (net (code "99") (name "unconnected-(U$1-Pad37{slash}A18)") (class "Default")
      (node (ref "U$1") (pin "37/A18") (pinfunction "37/A18_37/A18") (pintype "bidirectional"))
    )
    (net (code "100") (name "unconnected-(U$1-Pad38{slash}A19)") (class "Default")
      (node (ref "U$1") (pin "38/A19") (pinfunction "38/A19_38/A19") (pintype "bidirectional"))
    )
    (net (code "101") (name "unconnected-(U$1-Pad39{slash}A20)") (class "Default")
      (node (ref "U$1") (pin "39/A20") (pinfunction "39/A20_39/A20") (pintype "bidirectional"))
    )
    (net (code "102") (name "unconnected-(U$1-PadA10)") (class "Default")
      (node (ref "U$1") (pin "A10") (pinfunction "A10_A10") (pintype "bidirectional"))
    )
    (net (code "103") (name "unconnected-(U$1-PadA11)") (class "Default")
      (node (ref "U$1") (pin "A11") (pinfunction "A11_A11") (pintype "bidirectional"))
    )
    (net (code "104") (name "unconnected-(U$1-PadA22{slash}DAC1)") (class "Default")
      (node (ref "U$1") (pin "A22/DAC1") (pinfunction "A22/DAC1_A22/DAC1") (pintype "bidirectional"))
    )
    (net (code "105") (name "unconnected-(U$1-PadAREF)") (class "Default")
      (node (ref "U$1") (pin "AREF") (pinfunction "AREF_AREF") (pintype "bidirectional"))
    )
    (net (code "106") (name "unconnected-(U$1-PadGND2)") (class "Default")
      (node (ref "U$1") (pin "GND2") (pinfunction "GND2_GND2") (pintype "bidirectional"))
    )
    (net (code "107") (name "unconnected-(U$1-PadVUSB)") (class "Default")
      (node (ref "U$1") (pin "VUSB") (pinfunction "VUSB_VUSB") (pintype "bidirectional"))
    )
    (net (code "108") (name "unconnected-(U$4-PadINT)") (class "Default")
      (node (ref "U$4") (pin "INT") (pinfunction "INT_INT") (pintype "bidirectional"))
    )
    (net (code "109") (name "unconnected-(U$5-VREF-Pad8)") (class "Default")
      (node (ref "U$5") (pin "8") (pinfunction "VREF_8") (pintype "bidirectional"))
    )
  )
)
